# BatteryBoard.net
KiCad netlist of a schematic drawn in Altium Designer
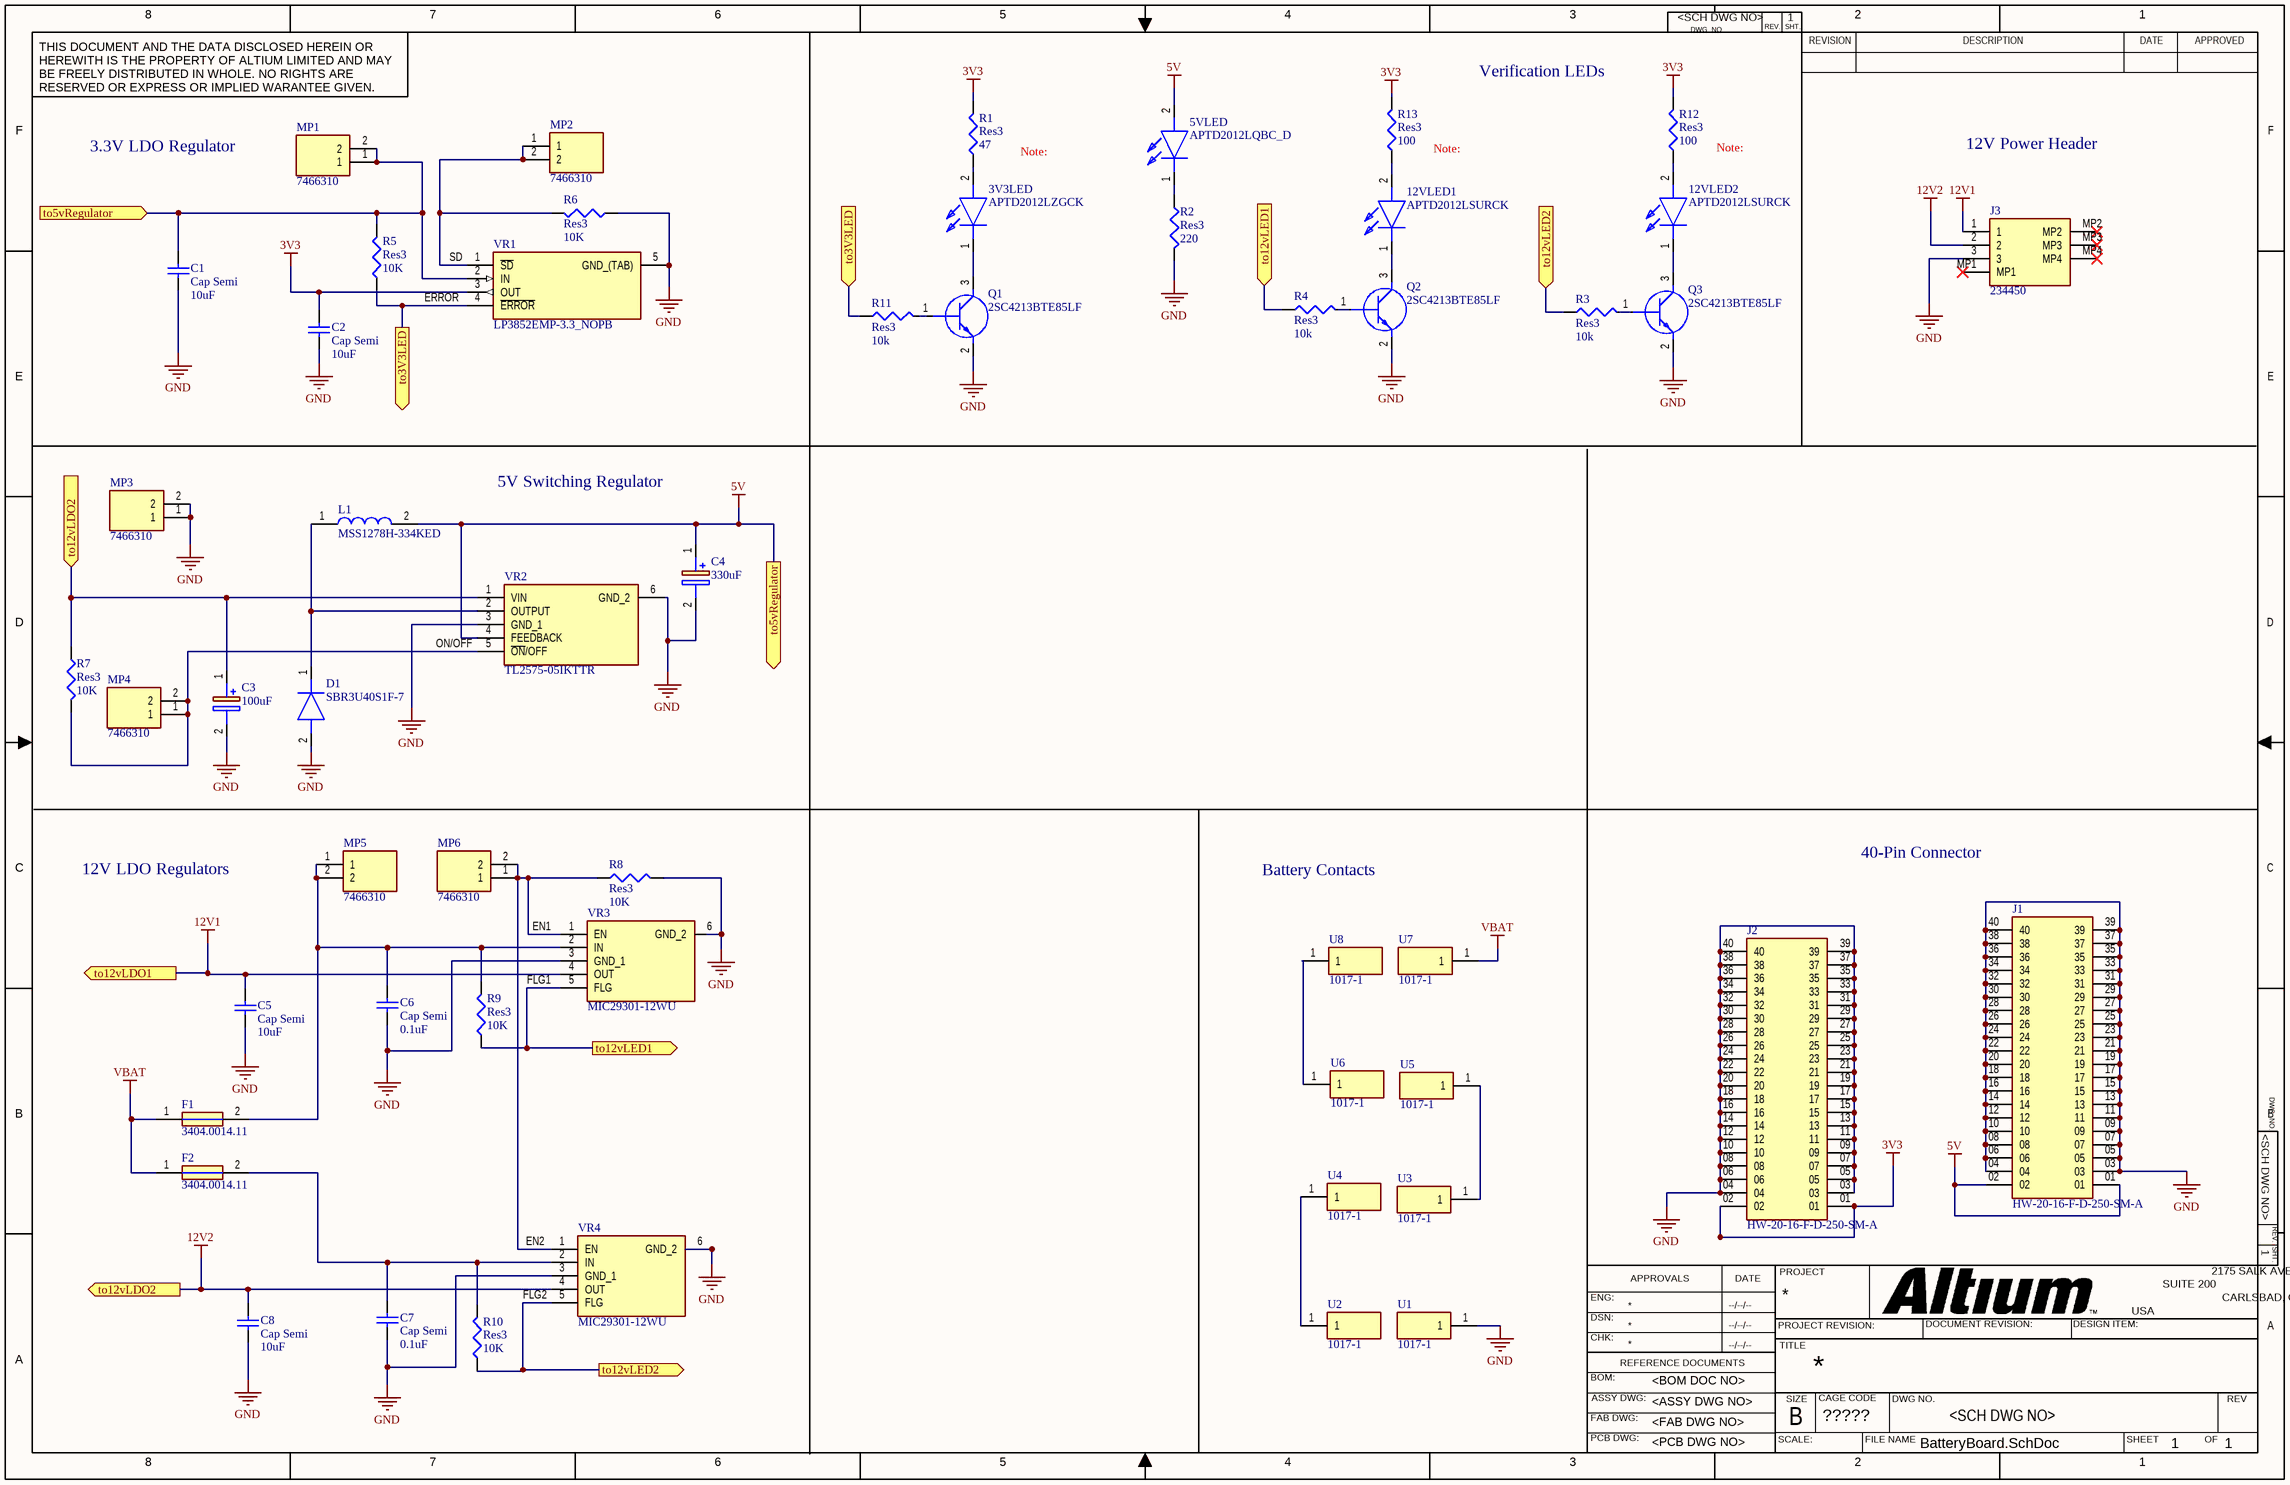
[diagram p0: BatteryBoard.SchDoc]

(export (version "E")
  (design (tool "Eeschema 10.0.6"))
  (components
    (comp (ref "3V3LED")
      (value "APTD2012LZGCK")
      (footprint "SamacSys:LEDC2012X105N")
      (description "LED")
      (fields (field (name "MOUSER PART NUMBER") "604-APTD2012LZGCK"))
      (libsource (lib "SamacSys") (part "APTD2012LZGCK"))
    )
    (comp (ref "5VLED")
      (value "APTD2012LQBC_D")
      (footprint "SamacSys:LEDC2012X120N")
      (description "LED")
      (fields
        (field (name "MANUFACTURER_PART_NUMBER") "APTD2012LQBC/D")
        (field (name "MOUSER PART NUMBER") "604-APTD2012LQBCD")
      )
      (libsource (lib "*") (part "APTD2012LQBC_D"))
    )
    (comp (ref "12VLED1")
      (value "APTD2012LSURCK")
      (footprint "SamacSys:LEDM2012X120N")
      (description "LED")
      (fields (field (name "MOUSER PART NUMBER") "604-APTD2012LSURCK"))
      (libsource (lib "*") (part "APTD2012LSURCK"))
    )
    (comp (ref "12VLED2")
      (value "APTD2012LSURCK")
      (footprint "SamacSys:LEDM2012X120N")
      (description "LED")
      (fields (field (name "MOUSER PART NUMBER") "604-APTD2012LSURCK"))
      (libsource (lib "*") (part "APTD2012LSURCK"))
    )
    (comp (ref "C1")
      (value "Cap Semi")
      (footprint "C1206")
      (description "Capacitor (Semiconductor SIM Model)")
      (fields (field (name "ALTIUM_VALUE") "10uF") (field (name "PUBLISHER") "Altium Limited"))
      (libsource (lib "Miscellaneous Devices") (part "Cap Semi"))
    )
    (comp (ref "C2")
      (value "Cap Semi")
      (footprint "C1206")
      (description "Capacitor (Semiconductor SIM Model)")
      (fields (field (name "ALTIUM_VALUE") "10uF") (field (name "PUBLISHER") "Altium Limited"))
      (libsource (lib "Miscellaneous Devices") (part "Cap Semi"))
    )
    (comp (ref "C3")
      (value "100uF")
      (footprint "SamacSys:EEEHP1H4R7P")
      (description "Capacitor Polarised")
      (fields
        (field (name "MANUFACTURER_PART_NUMBER") "EEE-FPE101XAL")
        (field (name "MOUSER PART NUMBER") "667-EEE-FPE101XAL")
      )
      (libsource (lib "*") (part "EEE-FPE101XAL"))
    )
    (comp (ref "C4")
      (value "330uF")
      (footprint "SamacSys:CAPAE660X800N")
      (description "Capacitor Polarised")
      (fields
        (field (name "MANUFACTURER_PART_NUMBER") "EMZR160ARA331MF80G")
        (field (name "MOUSER PART NUMBER") "661-EMZR160ARA331MF8")
      )
      (libsource (lib "*") (part "EMZR160ARA331MF80G"))
    )
    (comp (ref "C5")
      (value "Cap Semi")
      (footprint "C1206")
      (description "Capacitor (Semiconductor SIM Model)")
      (fields (field (name "ALTIUM_VALUE") "10uF") (field (name "PUBLISHER") "Altium Limited"))
      (libsource (lib "Miscellaneous Devices") (part "Cap Semi"))
    )
    (comp (ref "C6")
      (value "Cap Semi")
      (footprint "C1206")
      (description "Capacitor (Semiconductor SIM Model)")
      (fields (field (name "ALTIUM_VALUE") "0.1uF") (field (name "PUBLISHER") "Altium Limited"))
      (libsource (lib "Miscellaneous Devices") (part "Cap Semi"))
    )
    (comp (ref "C7")
      (value "Cap Semi")
      (footprint "C1206")
      (description "Capacitor (Semiconductor SIM Model)")
      (fields (field (name "ALTIUM_VALUE") "0.1uF") (field (name "PUBLISHER") "Altium Limited"))
      (libsource (lib "Miscellaneous Devices") (part "Cap Semi"))
    )
    (comp (ref "C8")
      (value "Cap Semi")
      (footprint "C1206")
      (description "Capacitor (Semiconductor SIM Model)")
      (fields (field (name "ALTIUM_VALUE") "10uF") (field (name "PUBLISHER") "Altium Limited"))
      (libsource (lib "Miscellaneous Devices") (part "Cap Semi"))
    )
    (comp (ref "D1")
      (value "SBR3U40S1F-7")
      (footprint "SamacSys:SODFL3518X115N")
      (description "Diode")
      (fields (field (name "MOUSER PART NUMBER") "621-SBR3U40S1F-7"))
      (libsource (lib "*") (part "SBR3U40S1F-7"))
    )
    (comp (ref "F1")
      (value "3404.0014.11")
      (footprint "SamacSys:FUSM7431X260N")
      (description "Fuse")
      (fields (field (name "MOUSER PART NUMBER") "693-3404.0014.11"))
      (libsource (lib "*") (part "3404.0014.11"))
    )
    (comp (ref "F2")
      (value "3404.0014.11")
      (footprint "SamacSys:FUSM7431X260N")
      (description "Fuse")
      (fields (field (name "MOUSER PART NUMBER") "693-3404.0014.11"))
      (libsource (lib "*") (part "3404.0014.11"))
    )
    (comp (ref "J1")
      (value "HW-20-16-F-D-250-SM-A")
      (footprint "SAMTEC_HW-20-16-F-D-250-SM-A")
      (libsource (lib "HW-20-16-F-D-250-SM-A") (part "HW-20-16-F-D-250-SM-A"))
    )
    (comp (ref "J2")
      (value "HW-20-16-F-D-250-SM-A")
      (footprint "SAMTEC_HW-20-16-F-D-250-SM-A")
      (libsource (lib "HW-20-16-F-D-250-SM-A") (part "HW-20-16-F-D-250-SM-A"))
    )
    (comp (ref "J3")
      (value "234450")
      (footprint "SamacSys:234450")
      (description "Connector")
      (fields (field (name "MOUSER PART NUMBER") "305-234450"))
      (libsource (lib "*") (part "234450"))
    )
    (comp (ref "L1")
      (value "MSS1278H-334KED")
      (footprint "SamacSys:MSS1278H334KED")
      (description "Inductor")
      (fields (field (name "MOUSER PART NUMBER") "994-MSS1278H-334KED"))
      (libsource (lib "*") (part "MSS1278H-334KED"))
    )
    (comp (ref "MP1")
      (value "7466310")
      (footprint "7466310")
      (description "Terminals WP-SMRA SMD w/Pins 5.5mm")
      (fields (field (name "MOUSER PART NUMBER") "710-7466310"))
      (libsource (lib "7466310") (part "7466310"))
    )
    (comp (ref "MP2")
      (value "7466310")
      (footprint "7466310")
      (description "Terminals WP-SMRA SMD w/Pins 5.5mm")
      (fields (field (name "MOUSER PART NUMBER") "710-7466310"))
      (libsource (lib "") (part "7466310_1"))
    )
    (comp (ref "MP3")
      (value "7466310")
      (footprint "7466310")
      (description "Terminals WP-SMRA SMD w/Pins 5.5mm")
      (fields (field (name "MOUSER PART NUMBER") "710-7466310"))
      (libsource (lib "7466310") (part "7466310"))
    )
    (comp (ref "MP4")
      (value "7466310")
      (footprint "7466310")
      (description "Terminals WP-SMRA SMD w/Pins 5.5mm")
      (fields (field (name "MOUSER PART NUMBER") "710-7466310"))
      (libsource (lib "7466310") (part "7466310"))
    )
    (comp (ref "MP5")
      (value "7466310")
      (footprint "7466310")
      (description "Terminals WP-SMRA SMD w/Pins 5.5mm")
      (fields (field (name "MOUSER PART NUMBER") "710-7466310"))
      (libsource (lib "") (part "7466310_1"))
    )
    (comp (ref "MP6")
      (value "7466310")
      (footprint "7466310")
      (description "Terminals WP-SMRA SMD w/Pins 5.5mm")
      (fields (field (name "MOUSER PART NUMBER") "710-7466310"))
      (libsource (lib "7466310") (part "7466310"))
    )
    (comp (ref "Q1")
      (value "2SC4213BTE85LF")
      (footprint "SamacSys:SOT65P210X110-3N")
      (description "Transistor BJT NPN")
      (fields (field (name "MOUSER PART NUMBER") "757-2SC4213BTE85LF"))
      (libsource (lib "*") (part "2SC4213BTE85LF"))
    )
    (comp (ref "Q2")
      (value "2SC4213BTE85LF")
      (footprint "SamacSys:SOT65P210X110-3N")
      (description "Transistor BJT NPN")
      (fields (field (name "MOUSER PART NUMBER") "757-2SC4213BTE85LF"))
      (libsource (lib "*") (part "2SC4213BTE85LF"))
    )
    (comp (ref "Q3")
      (value "2SC4213BTE85LF")
      (footprint "SamacSys:SOT65P210X110-3N")
      (description "Transistor BJT NPN")
      (fields (field (name "MOUSER PART NUMBER") "757-2SC4213BTE85LF"))
      (libsource (lib "*") (part "2SC4213BTE85LF"))
    )
    (comp (ref "R1")
      (value "Res3")
      (footprint "J1-0603")
      (description "Resistor")
      (fields (field (name "ALTIUM_VALUE") "47") (field (name "PUBLISHER") "Altium Limited"))
      (libsource (lib "Miscellaneous Devices") (part "Res3"))
    )
    (comp (ref "R2")
      (value "Res3")
      (footprint "J1-0603")
      (description "Resistor")
      (fields (field (name "ALTIUM_VALUE") "220") (field (name "PUBLISHER") "Altium Limited"))
      (libsource (lib "Miscellaneous Devices") (part "Res3"))
    )
    (comp (ref "R3")
      (value "Res3")
      (footprint "J1-0603")
      (description "Resistor")
      (fields (field (name "ALTIUM_VALUE") "10k") (field (name "PUBLISHER") "Altium Limited"))
      (libsource (lib "Miscellaneous Devices") (part "Res3"))
    )
    (comp (ref "R4")
      (value "Res3")
      (footprint "J1-0603")
      (description "Resistor")
      (fields (field (name "ALTIUM_VALUE") "10k") (field (name "PUBLISHER") "Altium Limited"))
      (libsource (lib "Miscellaneous Devices") (part "Res3"))
    )
    (comp (ref "R5")
      (value "Res3")
      (footprint "J1-0603")
      (description "Resistor")
      (fields (field (name "ALTIUM_VALUE") "10K") (field (name "PUBLISHER") "Altium Limited"))
      (libsource (lib "Miscellaneous Devices") (part "Res3"))
    )
    (comp (ref "R6")
      (value "Res3")
      (footprint "J1-0603")
      (description "Resistor")
      (fields (field (name "ALTIUM_VALUE") "10K") (field (name "PUBLISHER") "Altium Limited"))
      (libsource (lib "Miscellaneous Devices") (part "Res3"))
    )
    (comp (ref "R7")
      (value "Res3")
      (footprint "J1-0603")
      (description "Resistor")
      (fields (field (name "ALTIUM_VALUE") "10K") (field (name "PUBLISHER") "Altium Limited"))
      (libsource (lib "Miscellaneous Devices") (part "Res3"))
    )
    (comp (ref "R8")
      (value "Res3")
      (footprint "J1-0603")
      (description "Resistor")
      (fields (field (name "ALTIUM_VALUE") "10K") (field (name "PUBLISHER") "Altium Limited"))
      (libsource (lib "Miscellaneous Devices") (part "Res3"))
    )
    (comp (ref "R9")
      (value "Res3")
      (footprint "J1-0603")
      (description "Resistor")
      (fields (field (name "ALTIUM_VALUE") "10K") (field (name "PUBLISHER") "Altium Limited"))
      (libsource (lib "Miscellaneous Devices") (part "Res3"))
    )
    (comp (ref "R10")
      (value "Res3")
      (footprint "J1-0603")
      (description "Resistor")
      (fields (field (name "ALTIUM_VALUE") "10K") (field (name "PUBLISHER") "Altium Limited"))
      (libsource (lib "Miscellaneous Devices") (part "Res3"))
    )
    (comp (ref "R11")
      (value "Res3")
      (footprint "J1-0603")
      (description "Resistor")
      (fields (field (name "ALTIUM_VALUE") "10k") (field (name "PUBLISHER") "Altium Limited"))
      (libsource (lib "Miscellaneous Devices") (part "Res3"))
    )
    (comp (ref "R12")
      (value "Res3")
      (footprint "J1-0603")
      (description "Resistor")
      (fields (field (name "ALTIUM_VALUE") "100") (field (name "PUBLISHER") "Altium Limited"))
      (libsource (lib "Miscellaneous Devices") (part "Res3"))
    )
    (comp (ref "R13")
      (value "Res3")
      (footprint "J1-0603")
      (description "Resistor")
      (fields (field (name "ALTIUM_VALUE") "100") (field (name "PUBLISHER") "Altium Limited"))
      (libsource (lib "Miscellaneous Devices") (part "Res3"))
    )
    (comp (ref "U1")
      (value "1017-1")
      (footprint "SamacSys:10171")
      (description "Undefined or Miscellaneous")
      (fields (field (name "MOUSER PART NUMBER") "534-1017-1"))
      (libsource (lib "") (part "1017-1_1"))
    )
    (comp (ref "U2")
      (value "1017-1")
      (footprint "SamacSys:10171")
      (description "Undefined or Miscellaneous")
      (fields (field (name "MOUSER PART NUMBER") "534-1017-1"))
      (libsource (lib "SamacSys") (part "1017-1"))
    )
    (comp (ref "U3")
      (value "1017-1")
      (footprint "SamacSys:10171")
      (description "Undefined or Miscellaneous")
      (fields (field (name "MOUSER PART NUMBER") "534-1017-1"))
      (libsource (lib "") (part "1017-1_1"))
    )
    (comp (ref "U4")
      (value "1017-1")
      (footprint "SamacSys:10171")
      (description "Undefined or Miscellaneous")
      (fields (field (name "MOUSER PART NUMBER") "534-1017-1"))
      (libsource (lib "SamacSys") (part "1017-1"))
    )
    (comp (ref "U5")
      (value "1017-1")
      (footprint "SamacSys:10171")
      (description "Undefined or Miscellaneous")
      (fields (field (name "MOUSER PART NUMBER") "534-1017-1"))
      (libsource (lib "") (part "1017-1_1"))
    )
    (comp (ref "U6")
      (value "1017-1")
      (footprint "SamacSys:10171")
      (description "Undefined or Miscellaneous")
      (fields (field (name "MOUSER PART NUMBER") "534-1017-1"))
      (libsource (lib "SamacSys") (part "1017-1"))
    )
    (comp (ref "U7")
      (value "1017-1")
      (footprint "SamacSys:10171")
      (description "Undefined or Miscellaneous")
      (fields (field (name "MOUSER PART NUMBER") "534-1017-1"))
      (libsource (lib "") (part "1017-1_1"))
    )
    (comp (ref "U8")
      (value "1017-1")
      (footprint "SamacSys:10171")
      (description "Undefined or Miscellaneous")
      (fields (field (name "MOUSER PART NUMBER") "534-1017-1"))
      (libsource (lib "SamacSys") (part "1017-1"))
    )
    (comp (ref "VR1")
      (value "LP3852EMP-3.3_NOPB")
      (footprint "SamacSys:SOT150P700X180-5N")
      (description "Integrated Circuit")
      (fields
        (field (name "MANUFACTURER_PART_NUMBER") "LP3852EMP-3.3/NOPB")
        (field (name "MOUSER PART NUMBER") "926-LP3852EMP33NOPB")
      )
      (libsource (lib "*") (part "LP3852EMP-3.3_NOPB"))
    )
    (comp (ref "VR2")
      (value "TL2575-05IKTTR")
      (footprint "SamacSys:TL1963AQKTTRQ1")
      (description "Integrated Circuit")
      (fields (field (name "MOUSER PART NUMBER") "595-TL2575-05IKTTR"))
      (libsource (lib "*") (part "TL2575-05IKTTR"))
    )
    (comp (ref "VR3")
      (value "MIC29301-12WU")
      (footprint "SamacSys:MIC2930133WUTR")
      (description "Integrated Circuit")
      (fields
        (field (name "MANUFACTURER_PART_NUMBER") "MIC29301-3.3WU-TR")
        (field (name "MOUSER PART NUMBER") "998-MIC29301-3.3WUTR")
      )
      (libsource (lib "SamacSys") (part "MIC29301-3.3WU-TR"))
    )
    (comp (ref "VR4")
      (value "MIC29301-12WU")
      (footprint "SamacSys:MIC2930133WUTR")
      (description "Integrated Circuit")
      (fields
        (field (name "MANUFACTURER_PART_NUMBER") "MIC29301-3.3WU-TR")
        (field (name "MOUSER PART NUMBER") "998-MIC29301-3.3WUTR")
      )
      (libsource (lib "SamacSys") (part "MIC29301-3.3WU-TR"))
    )
  )
  (nets
    (net (code "1") (name "/EN1") (class "Default")
      (node (ref "MP6") (pin "1") (pinfunction "1_1") (pintype "passive"))
      (node (ref "MP6") (pin "2") (pinfunction "2_2") (pintype "passive"))
      (node (ref "R8") (pin "1") (pinfunction "1_1") (pintype "passive"))
      (node (ref "VR3") (pin "1") (pinfunction "EN_1") (pintype "passive"))
      (node (ref "VR4") (pin "1") (pinfunction "EN_1") (pintype "passive"))
    )
    (net (code "2") (name "/ERROR") (class "Default")
      (node (ref "R11") (pin "1") (pinfunction "1_1") (pintype "passive"))
      (node (ref "R5") (pin "1") (pinfunction "1_1") (pintype "passive"))
      (node (ref "VR1") (pin "4") (pinfunction "~{ERROR}_4") (pintype "passive"))
    )
    (net (code "3") (name "/FLG1") (class "Default")
      (node (ref "R4") (pin "1") (pinfunction "1_1") (pintype "passive"))
      (node (ref "R9") (pin "1") (pinfunction "1_1") (pintype "passive"))
      (node (ref "VR3") (pin "5") (pinfunction "FLG_5") (pintype "passive"))
    )
    (net (code "4") (name "/FLG2") (class "Default")
      (node (ref "R10") (pin "1") (pinfunction "1_1") (pintype "passive"))
      (node (ref "R3") (pin "1") (pinfunction "1_1") (pintype "passive"))
      (node (ref "VR4") (pin "5") (pinfunction "FLG_5") (pintype "passive"))
    )
    (net (code "5") (name "/ON{slash}OFF") (class "Default")
      (node (ref "MP4") (pin "1") (pinfunction "1_1") (pintype "passive"))
      (node (ref "MP4") (pin "2") (pinfunction "2_2") (pintype "passive"))
      (node (ref "R7") (pin "2") (pinfunction "2_2") (pintype "passive"))
      (node (ref "VR2") (pin "5") (pinfunction "~{ON}/OFF_5") (pintype "passive"))
    )
    (net (code "6") (name "/SD") (class "Default")
      (node (ref "MP2") (pin "1") (pinfunction "1_1") (pintype "passive"))
      (node (ref "MP2") (pin "2") (pinfunction "2_2") (pintype "passive"))
      (node (ref "R6") (pin "2") (pinfunction "2_2") (pintype "passive"))
      (node (ref "VR1") (pin "1") (pinfunction "~{SD}_1") (pintype "passive"))
    )
    (net (code "7") (name "3V3") (class "Default")
      (node (ref "C2") (pin "2") (pinfunction "2_2") (pintype "passive"))
      (node (ref "J2") (pin "01") (pinfunction "01_01") (pintype "passive"))
      (node (ref "J2") (pin "02") (pinfunction "02_02") (pintype "passive"))
      (node (ref "R1") (pin "2") (pinfunction "2_2") (pintype "passive"))
      (node (ref "R12") (pin "2") (pinfunction "2_2") (pintype "passive"))
      (node (ref "R13") (pin "2") (pinfunction "2_2") (pintype "passive"))
      (node (ref "VR1") (pin "3") (pinfunction "OUT_3") (pintype "output"))
    )
    (net (code "8") (name "5V") (class "Default")
      (node (ref "5VLED") (pin "2") (pinfunction "A_2") (pintype "passive"))
      (node (ref "C1") (pin "2") (pinfunction "2_2") (pintype "passive"))
      (node (ref "C4") (pin "1") (pinfunction "+_1") (pintype "passive"))
      (node (ref "J1") (pin "01") (pinfunction "01_01") (pintype "passive"))
      (node (ref "J1") (pin "02") (pinfunction "02_02") (pintype "passive"))
      (node (ref "L1") (pin "2") (pinfunction "2_2") (pintype "passive"))
      (node (ref "MP1") (pin "1") (pinfunction "1_1") (pintype "passive"))
      (node (ref "MP1") (pin "2") (pinfunction "2_2") (pintype "passive"))
      (node (ref "R5") (pin "2") (pinfunction "2_2") (pintype "passive"))
      (node (ref "VR1") (pin "2") (pinfunction "IN_2") (pintype "input"))
      (node (ref "VR2") (pin "4") (pinfunction "FEEDBACK_4") (pintype "passive"))
    )
    (net (code "9") (name "12V1") (class "Default")
      (node (ref "C5") (pin "2") (pinfunction "2_2") (pintype "passive"))
      (node (ref "J3") (pin "1") (pinfunction "1_1") (pintype "passive"))
      (node (ref "VR3") (pin "4") (pinfunction "OUT_4") (pintype "passive"))
    )
    (net (code "10") (name "12V2") (class "Default")
      (node (ref "C3") (pin "1") (pinfunction "+_1") (pintype "passive"))
      (node (ref "C8") (pin "2") (pinfunction "2_2") (pintype "passive"))
      (node (ref "J3") (pin "2") (pinfunction "2_2") (pintype "passive"))
      (node (ref "R7") (pin "1") (pinfunction "1_1") (pintype "passive"))
      (node (ref "VR2") (pin "1") (pinfunction "VIN_1") (pintype "passive"))
      (node (ref "VR4") (pin "4") (pinfunction "OUT_4") (pintype "passive"))
    )
    (net (code "11") (name "GND") (class "Default")
      (node (ref "C1") (pin "1") (pinfunction "1_1") (pintype "passive"))
      (node (ref "C2") (pin "1") (pinfunction "1_1") (pintype "passive"))
      (node (ref "C3") (pin "2") (pinfunction "-_2") (pintype "passive"))
      (node (ref "C4") (pin "2") (pinfunction "-_2") (pintype "passive"))
      (node (ref "C5") (pin "1") (pinfunction "1_1") (pintype "passive"))
      (node (ref "C6") (pin "2") (pinfunction "2_2") (pintype "passive"))
      (node (ref "C7") (pin "2") (pinfunction "2_2") (pintype "passive"))
      (node (ref "C8") (pin "1") (pinfunction "1_1") (pintype "passive"))
      (node (ref "D1") (pin "2") (pinfunction "A_2") (pintype "passive"))
      (node (ref "J1") (pin "03") (pinfunction "03_03") (pintype "passive"))
      (node (ref "J1") (pin "04") (pinfunction "04_04") (pintype "passive"))
      (node (ref "J1") (pin "05") (pinfunction "05_05") (pintype "passive"))
      (node (ref "J1") (pin "06") (pinfunction "06_06") (pintype "passive"))
      (node (ref "J1") (pin "07") (pinfunction "07_07") (pintype "passive"))
      (node (ref "J1") (pin "08") (pinfunction "08_08") (pintype "passive"))
      (node (ref "J1") (pin "09") (pinfunction "09_09") (pintype "passive"))
      (node (ref "J1") (pin "10") (pinfunction "10_10") (pintype "passive"))
      (node (ref "J1") (pin "11") (pinfunction "11_11") (pintype "passive"))
      (node (ref "J1") (pin "12") (pinfunction "12_12") (pintype "passive"))
      (node (ref "J1") (pin "13") (pinfunction "13_13") (pintype "passive"))
      (node (ref "J1") (pin "14") (pinfunction "14_14") (pintype "passive"))
      (node (ref "J1") (pin "15") (pinfunction "15_15") (pintype "passive"))
      (node (ref "J1") (pin "16") (pinfunction "16_16") (pintype "passive"))
      (node (ref "J1") (pin "17") (pinfunction "17_17") (pintype "passive"))
      (node (ref "J1") (pin "18") (pinfunction "18_18") (pintype "passive"))
      (node (ref "J1") (pin "19") (pinfunction "19_19") (pintype "passive"))
      (node (ref "J1") (pin "20") (pinfunction "20_20") (pintype "passive"))
      (node (ref "J1") (pin "21") (pinfunction "21_21") (pintype "passive"))
      (node (ref "J1") (pin "22") (pinfunction "22_22") (pintype "passive"))
      (node (ref "J1") (pin "23") (pinfunction "23_23") (pintype "passive"))
      (node (ref "J1") (pin "24") (pinfunction "24_24") (pintype "passive"))
      (node (ref "J1") (pin "25") (pinfunction "25_25") (pintype "passive"))
      (node (ref "J1") (pin "26") (pinfunction "26_26") (pintype "passive"))
      (node (ref "J1") (pin "27") (pinfunction "27_27") (pintype "passive"))
      (node (ref "J1") (pin "28") (pinfunction "28_28") (pintype "passive"))
      (node (ref "J1") (pin "29") (pinfunction "29_29") (pintype "passive"))
      (node (ref "J1") (pin "30") (pinfunction "30_30") (pintype "passive"))
      (node (ref "J1") (pin "31") (pinfunction "31_31") (pintype "passive"))
      (node (ref "J1") (pin "32") (pinfunction "32_32") (pintype "passive"))
      (node (ref "J1") (pin "33") (pinfunction "33_33") (pintype "passive"))
      (node (ref "J1") (pin "34") (pinfunction "34_34") (pintype "passive"))
      (node (ref "J1") (pin "35") (pinfunction "35_35") (pintype "passive"))
      (node (ref "J1") (pin "36") (pinfunction "36_36") (pintype "passive"))
      (node (ref "J1") (pin "37") (pinfunction "37_37") (pintype "passive"))
      (node (ref "J1") (pin "38") (pinfunction "38_38") (pintype "passive"))
      (node (ref "J1") (pin "39") (pinfunction "39_39") (pintype "passive"))
      (node (ref "J1") (pin "40") (pinfunction "40_40") (pintype "passive"))
      (node (ref "J2") (pin "03") (pinfunction "03_03") (pintype "passive"))
      (node (ref "J2") (pin "04") (pinfunction "04_04") (pintype "passive"))
      (node (ref "J2") (pin "05") (pinfunction "05_05") (pintype "passive"))
      (node (ref "J2") (pin "06") (pinfunction "06_06") (pintype "passive"))
      (node (ref "J2") (pin "07") (pinfunction "07_07") (pintype "passive"))
      (node (ref "J2") (pin "08") (pinfunction "08_08") (pintype "passive"))
      (node (ref "J2") (pin "09") (pinfunction "09_09") (pintype "passive"))
      (node (ref "J2") (pin "10") (pinfunction "10_10") (pintype "passive"))
      (node (ref "J2") (pin "11") (pinfunction "11_11") (pintype "passive"))
      (node (ref "J2") (pin "12") (pinfunction "12_12") (pintype "passive"))
      (node (ref "J2") (pin "13") (pinfunction "13_13") (pintype "passive"))
      (node (ref "J2") (pin "14") (pinfunction "14_14") (pintype "passive"))
      (node (ref "J2") (pin "15") (pinfunction "15_15") (pintype "passive"))
      (node (ref "J2") (pin "16") (pinfunction "16_16") (pintype "passive"))
      (node (ref "J2") (pin "17") (pinfunction "17_17") (pintype "passive"))
      (node (ref "J2") (pin "18") (pinfunction "18_18") (pintype "passive"))
      (node (ref "J2") (pin "19") (pinfunction "19_19") (pintype "passive"))
      (node (ref "J2") (pin "20") (pinfunction "20_20") (pintype "passive"))
      (node (ref "J2") (pin "21") (pinfunction "21_21") (pintype "passive"))
      (node (ref "J2") (pin "22") (pinfunction "22_22") (pintype "passive"))
      (node (ref "J2") (pin "23") (pinfunction "23_23") (pintype "passive"))
      (node (ref "J2") (pin "24") (pinfunction "24_24") (pintype "passive"))
      (node (ref "J2") (pin "25") (pinfunction "25_25") (pintype "passive"))
      (node (ref "J2") (pin "26") (pinfunction "26_26") (pintype "passive"))
      (node (ref "J2") (pin "27") (pinfunction "27_27") (pintype "passive"))
      (node (ref "J2") (pin "28") (pinfunction "28_28") (pintype "passive"))
      (node (ref "J2") (pin "29") (pinfunction "29_29") (pintype "passive"))
      (node (ref "J2") (pin "30") (pinfunction "30_30") (pintype "passive"))
      (node (ref "J2") (pin "31") (pinfunction "31_31") (pintype "passive"))
      (node (ref "J2") (pin "32") (pinfunction "32_32") (pintype "passive"))
      (node (ref "J2") (pin "33") (pinfunction "33_33") (pintype "passive"))
      (node (ref "J2") (pin "34") (pinfunction "34_34") (pintype "passive"))
      (node (ref "J2") (pin "35") (pinfunction "35_35") (pintype "passive"))
      (node (ref "J2") (pin "36") (pinfunction "36_36") (pintype "passive"))
      (node (ref "J2") (pin "37") (pinfunction "37_37") (pintype "passive"))
      (node (ref "J2") (pin "38") (pinfunction "38_38") (pintype "passive"))
      (node (ref "J2") (pin "39") (pinfunction "39_39") (pintype "passive"))
      (node (ref "J2") (pin "40") (pinfunction "40_40") (pintype "passive"))
      (node (ref "J3") (pin "3") (pinfunction "3_3") (pintype "passive"))
      (node (ref "MP3") (pin "1") (pinfunction "1_1") (pintype "passive"))
      (node (ref "MP3") (pin "2") (pinfunction "2_2") (pintype "passive"))
      (node (ref "Q1") (pin "2") (pinfunction "E_2") (pintype "passive"))
      (node (ref "Q2") (pin "2") (pinfunction "E_2") (pintype "passive"))
      (node (ref "Q3") (pin "2") (pinfunction "E_2") (pintype "passive"))
      (node (ref "R2") (pin "2") (pinfunction "2_2") (pintype "passive"))
      (node (ref "R6") (pin "1") (pinfunction "1_1") (pintype "passive"))
      (node (ref "R8") (pin "2") (pinfunction "2_2") (pintype "passive"))
      (node (ref "U1") (pin "1") (pinfunction "1_1") (pintype "passive"))
      (node (ref "VR1") (pin "5") (pinfunction "GND_(TAB)_5") (pintype "power_in"))
      (node (ref "VR2") (pin "3") (pinfunction "GND_1_3") (pintype "passive"))
      (node (ref "VR2") (pin "6") (pinfunction "GND_2_6") (pintype "passive"))
      (node (ref "VR3") (pin "3") (pinfunction "GND_1_3") (pintype "passive"))
      (node (ref "VR3") (pin "6") (pinfunction "GND_2_6") (pintype "passive"))
      (node (ref "VR4") (pin "3") (pinfunction "GND_1_3") (pintype "passive"))
      (node (ref "VR4") (pin "6") (pinfunction "GND_2_6") (pintype "passive"))
    )
    (net (code "12") (name "Net-(3V3LED-A)") (class "Default")
      (node (ref "3V3LED") (pin "2") (pinfunction "A_2") (pintype "passive"))
      (node (ref "R1") (pin "1") (pinfunction "1_1") (pintype "passive"))
    )
    (net (code "13") (name "Net-(3V3LED-K)") (class "Default")
      (node (ref "3V3LED") (pin "1") (pinfunction "K_1") (pintype "passive"))
      (node (ref "Q1") (pin "3") (pinfunction "C_3") (pintype "passive"))
    )
    (net (code "14") (name "Net-(5VLED-K)") (class "Default")
      (node (ref "5VLED") (pin "1") (pinfunction "K_1") (pintype "passive"))
      (node (ref "R2") (pin "1") (pinfunction "1_1") (pintype "passive"))
    )
    (net (code "15") (name "Net-(12VLED1-A)") (class "Default")
      (node (ref "12VLED1") (pin "2") (pinfunction "A_2") (pintype "passive"))
      (node (ref "R13") (pin "1") (pinfunction "1_1") (pintype "passive"))
    )
    (net (code "16") (name "Net-(12VLED1-K)") (class "Default")
      (node (ref "12VLED1") (pin "1") (pinfunction "K_1") (pintype "passive"))
      (node (ref "Q2") (pin "3") (pinfunction "C_3") (pintype "passive"))
    )
    (net (code "17") (name "Net-(12VLED2-A)") (class "Default")
      (node (ref "12VLED2") (pin "2") (pinfunction "A_2") (pintype "passive"))
      (node (ref "R12") (pin "1") (pinfunction "1_1") (pintype "passive"))
    )
    (net (code "18") (name "Net-(12VLED2-K)") (class "Default")
      (node (ref "12VLED2") (pin "1") (pinfunction "K_1") (pintype "passive"))
      (node (ref "Q3") (pin "3") (pinfunction "C_3") (pintype "passive"))
    )
    (net (code "19") (name "Net-(D1-K)") (class "Default")
      (node (ref "D1") (pin "1") (pinfunction "K_1") (pintype "passive"))
      (node (ref "L1") (pin "1") (pinfunction "1_1") (pintype "passive"))
      (node (ref "VR2") (pin "2") (pinfunction "OUTPUT_2") (pintype "passive"))
    )
    (net (code "20") (name "Net-(Q1-B)") (class "Default")
      (node (ref "Q1") (pin "1") (pinfunction "B_1") (pintype "passive"))
      (node (ref "R11") (pin "2") (pinfunction "2_2") (pintype "passive"))
    )
    (net (code "21") (name "Net-(Q2-B)") (class "Default")
      (node (ref "Q2") (pin "1") (pinfunction "B_1") (pintype "passive"))
      (node (ref "R4") (pin "2") (pinfunction "2_2") (pintype "passive"))
    )
    (net (code "22") (name "Net-(Q3-B)") (class "Default")
      (node (ref "Q3") (pin "1") (pinfunction "B_1") (pintype "passive"))
      (node (ref "R3") (pin "2") (pinfunction "2_2") (pintype "passive"))
    )
    (net (code "23") (name "Net-(U2-Pad1)") (class "Default")
      (node (ref "U2") (pin "1") (pinfunction "1_1") (pintype "passive"))
      (node (ref "U4") (pin "1") (pinfunction "1_1") (pintype "passive"))
    )
    (net (code "24") (name "Net-(U3-Pad1)") (class "Default")
      (node (ref "U3") (pin "1") (pinfunction "1_1") (pintype "passive"))
      (node (ref "U5") (pin "1") (pinfunction "1_1") (pintype "passive"))
    )
    (net (code "25") (name "Net-(U6-Pad1)") (class "Default")
      (node (ref "U6") (pin "1") (pinfunction "1_1") (pintype "passive"))
      (node (ref "U8") (pin "1") (pinfunction "1_1") (pintype "passive"))
    )
    (net (code "26") (name "Net-(VR3-IN)") (class "Default")
      (node (ref "C6") (pin "1") (pinfunction "1_1") (pintype "passive"))
      (node (ref "F1") (pin "2") (pinfunction "2_2") (pintype "passive"))
      (node (ref "MP5") (pin "1") (pinfunction "1_1") (pintype "passive"))
      (node (ref "MP5") (pin "2") (pinfunction "2_2") (pintype "passive"))
      (node (ref "R9") (pin "2") (pinfunction "2_2") (pintype "passive"))
      (node (ref "VR3") (pin "2") (pinfunction "IN_2") (pintype "passive"))
    )
    (net (code "27") (name "Net-(VR4-IN)") (class "Default")
      (node (ref "C7") (pin "1") (pinfunction "1_1") (pintype "passive"))
      (node (ref "F2") (pin "2") (pinfunction "2_2") (pintype "passive"))
      (node (ref "R10") (pin "2") (pinfunction "2_2") (pintype "passive"))
      (node (ref "VR4") (pin "2") (pinfunction "IN_2") (pintype "passive"))
    )
    (net (code "28") (name "VBAT") (class "Default")
      (node (ref "F1") (pin "1") (pinfunction "1_1") (pintype "passive"))
      (node (ref "F2") (pin "1") (pinfunction "1_1") (pintype "passive"))
      (node (ref "U7") (pin "1") (pinfunction "1_1") (pintype "passive"))
    )
    (net (code "29") (name "unconnected-(J3-PadMP1)") (class "Default")
      (node (ref "J3") (pin "MP1") (pinfunction "MP1_MP1") (pintype "passive+no_connect"))
    )
    (net (code "30") (name "unconnected-(J3-PadMP2)") (class "Default")
      (node (ref "J3") (pin "MP2") (pinfunction "MP2_MP2") (pintype "passive+no_connect"))
    )
    (net (code "31") (name "unconnected-(J3-PadMP3)") (class "Default")
      (node (ref "J3") (pin "MP3") (pinfunction "MP3_MP3") (pintype "passive+no_connect"))
    )
    (net (code "32") (name "unconnected-(J3-PadMP4)") (class "Default")
      (node (ref "J3") (pin "MP4") (pinfunction "MP4_MP4") (pintype "passive+no_connect"))
    )
  )
)
